# NoteGenerator.net
KiCad netlist of a schematic drawn in EAGLE
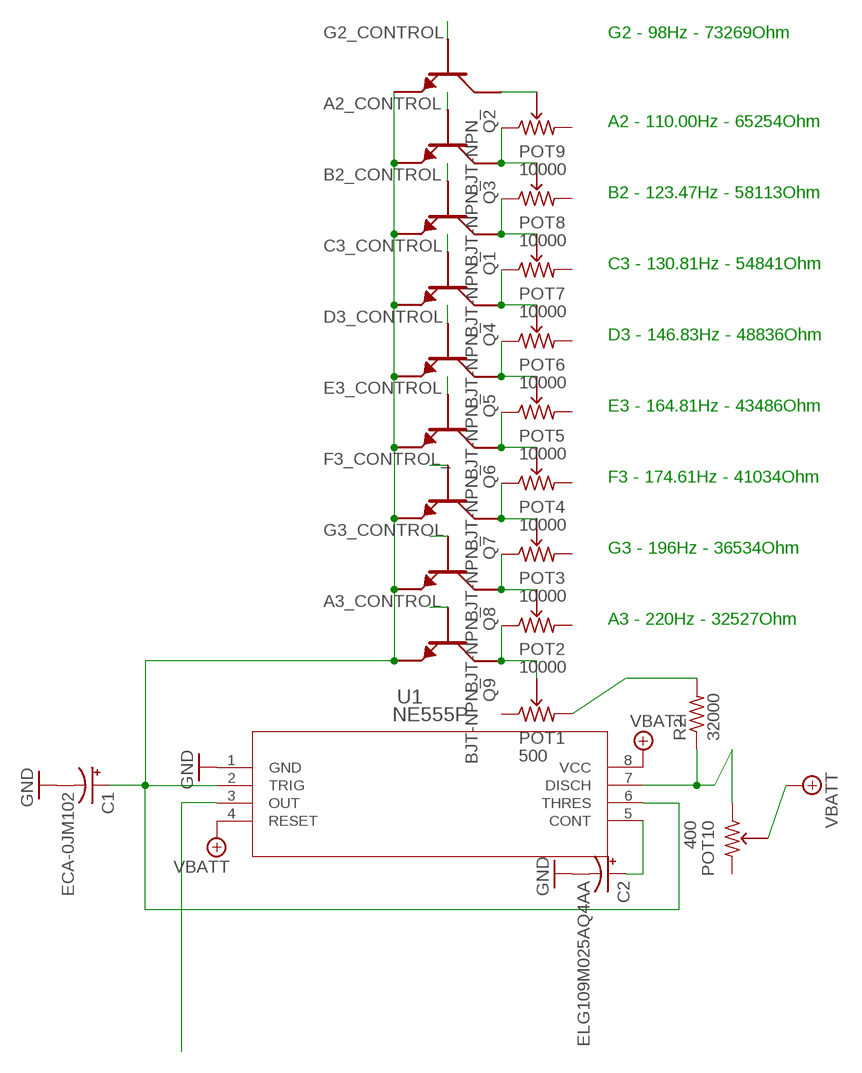
[diagram p0: schematic, sheet 1]

(export (version "E")
  (design (tool "Eeschema 10.0.6"))
  (components
    (comp (ref "C1")
      (value "ECA-0JM102")
      (footprint "eagle-import:PCAP_8X112")
      (fields (field (name "MANUFACTURER_PART_NUMBER") "ECA0JM102"))
      (libsource (lib "eagle-import") (part "ECA-0JM102"))
    )
    (comp (ref "C2")
      (value "ELG109M025AQ4AA")
      (footprint "eagle-import:PCAP_8X112")
      (fields (field (name "MANUFACTURER_PART_NUMBER") "ECA0JM102"))
      (libsource (lib "eagle-import") (part "ELG109M025AQ4AA"))
    )
    (comp (ref "POT1")
      (value "500")
      (footprint "eagle-import:PVG3G")
      (fields (field (name "POWER") "0.25W") (field (name "TOLERANCE") "±20%"))
      (libsource (lib "eagle-import") (part "PVG3"))
    )
    (comp (ref "POT2")
      (value "10000")
      (footprint "eagle-import:PVG3G")
      (fields (field (name "POWER") "0.25W") (field (name "TOLERANCE") "±20%"))
      (libsource (lib "eagle-import") (part "PVG3"))
    )
    (comp (ref "POT3")
      (value "10000")
      (footprint "eagle-import:PVG3G")
      (fields (field (name "POWER") "0.25W") (field (name "TOLERANCE") "±20%"))
      (libsource (lib "eagle-import") (part "PVG3"))
    )
    (comp (ref "POT4")
      (value "10000")
      (footprint "eagle-import:PVG3G")
      (fields (field (name "POWER") "0.25W") (field (name "TOLERANCE") "±20%"))
      (libsource (lib "eagle-import") (part "PVG3"))
    )
    (comp (ref "POT5")
      (value "10000")
      (footprint "eagle-import:PVG3G")
      (fields (field (name "POWER") "0.25W") (field (name "TOLERANCE") "±20%"))
      (libsource (lib "eagle-import") (part "PVG3"))
    )
    (comp (ref "POT6")
      (value "10000")
      (footprint "eagle-import:PVG3G")
      (fields (field (name "POWER") "0.25W") (field (name "TOLERANCE") "±20%"))
      (libsource (lib "eagle-import") (part "PVG3"))
    )
    (comp (ref "POT7")
      (value "10000")
      (footprint "eagle-import:PVG3G")
      (fields (field (name "POWER") "0.25W") (field (name "TOLERANCE") "±20%"))
      (libsource (lib "eagle-import") (part "PVG3"))
    )
    (comp (ref "POT8")
      (value "10000")
      (footprint "eagle-import:PVG3G")
      (fields (field (name "POWER") "0.25W") (field (name "TOLERANCE") "±20%"))
      (libsource (lib "eagle-import") (part "PVG3"))
    )
    (comp (ref "POT9")
      (value "10000")
      (footprint "eagle-import:PVG3G")
      (fields (field (name "POWER") "0.25W") (field (name "TOLERANCE") "±20%"))
      (libsource (lib "eagle-import") (part "PVG3"))
    )
    (comp (ref "POT10")
      (value "400")
      (footprint "eagle-import:PVG3G")
      (fields (field (name "POWER") "0.25W") (field (name "TOLERANCE") "±20%"))
      (libsource (lib "eagle-import") (part "PVG3"))
    )
    (comp (ref "Q1")
      (value "BJT-NPN_")
      (footprint "eagle-import:SOT-23-3")
      (libsource (lib "eagle-import") (part "BJT-NPN_"))
    )
    (comp (ref "Q2")
      (value "BJT-NPN_")
      (footprint "eagle-import:SOT-23-3")
      (libsource (lib "eagle-import") (part "BJT-NPN_"))
    )
    (comp (ref "Q3")
      (value "BJT-NPN_")
      (footprint "eagle-import:SOT-23-3")
      (libsource (lib "eagle-import") (part "BJT-NPN_"))
    )
    (comp (ref "Q4")
      (value "BJT-NPN_")
      (footprint "eagle-import:SOT-23-3")
      (libsource (lib "eagle-import") (part "BJT-NPN_"))
    )
    (comp (ref "Q5")
      (value "BJT-NPN_")
      (footprint "eagle-import:SOT-23-3")
      (libsource (lib "eagle-import") (part "BJT-NPN_"))
    )
    (comp (ref "Q6")
      (value "BJT-NPN_")
      (footprint "eagle-import:SOT-23-3")
      (libsource (lib "eagle-import") (part "BJT-NPN_"))
    )
    (comp (ref "Q7")
      (value "BJT-NPN_")
      (footprint "eagle-import:SOT-23-3")
      (libsource (lib "eagle-import") (part "BJT-NPN_"))
    )
    (comp (ref "Q8")
      (value "BJT-NPN_")
      (footprint "eagle-import:SOT-23-3")
      (libsource (lib "eagle-import") (part "BJT-NPN_"))
    )
    (comp (ref "Q9")
      (value "BJT-NPN_")
      (footprint "eagle-import:SOT-23-3")
      (libsource (lib "eagle-import") (part "BJT-NPN_"))
    )
    (comp (ref "R2")
      (value "32000")
      (footprint "eagle-import:RC0805N")
      (libsource (lib "eagle-import") (part "ERJ-L06KF50MV"))
    )
    (comp (ref "U1")
      (value "NE555P")
      (footprint "eagle-import:P8")
      (fields (field (name "GENERIC_PART_NUMBER") "NE555") (field (name "MANUFACTURER") "Texas Instruments"))
      (libsource (lib "eagle-import") (part "NE555P"))
    )
  )
  (nets
    (net (code "1") (name "/A2_CONTROL") (class "Default")
      (node (ref "Q3") (pin "1") (pinfunction "B_1") (pintype "bidirectional"))
    )
    (net (code "2") (name "/A3_CONTROL") (class "Default")
      (node (ref "Q9") (pin "1") (pinfunction "B_1") (pintype "bidirectional"))
    )
    (net (code "3") (name "/B2_CONTROL") (class "Default")
      (node (ref "Q1") (pin "1") (pinfunction "B_1") (pintype "bidirectional"))
    )
    (net (code "4") (name "/C3_CONTROL") (class "Default")
      (node (ref "Q4") (pin "1") (pinfunction "B_1") (pintype "bidirectional"))
    )
    (net (code "5") (name "/D3_CONTROL") (class "Default")
      (node (ref "Q5") (pin "1") (pinfunction "B_1") (pintype "bidirectional"))
    )
    (net (code "6") (name "/E3_CONTROL") (class "Default")
      (node (ref "Q6") (pin "1") (pinfunction "B_1") (pintype "bidirectional"))
    )
    (net (code "7") (name "/F3_CONTROL_") (class "Default")
      (node (ref "Q7") (pin "1") (pinfunction "B_1") (pintype "bidirectional"))
    )
    (net (code "8") (name "/G2_CONTROL") (class "Default")
      (node (ref "Q2") (pin "1") (pinfunction "B_1") (pintype "bidirectional"))
    )
    (net (code "9") (name "/G3_CONTROL") (class "Default")
      (node (ref "Q8") (pin "1") (pinfunction "B_1") (pintype "bidirectional"))
    )
    (net (code "10") (name "GND") (class "Default")
      (node (ref "C1") (pin "2") (pinfunction "-_2") (pintype "passive"))
      (node (ref "C2") (pin "2") (pinfunction "-_2") (pintype "passive"))
      (node (ref "U1") (pin "1") (pinfunction "GND_1") (pintype "power_in"))
    )
    (net (code "11") (name "Net-(C1-+)") (class "Default")
      (node (ref "C1") (pin "1") (pinfunction "+_1") (pintype "passive"))
      (node (ref "Q1") (pin "2") (pinfunction "E_2") (pintype "bidirectional"))
      (node (ref "Q2") (pin "2") (pinfunction "E_2") (pintype "bidirectional"))
      (node (ref "Q3") (pin "2") (pinfunction "E_2") (pintype "bidirectional"))
      (node (ref "Q4") (pin "2") (pinfunction "E_2") (pintype "bidirectional"))
      (node (ref "Q5") (pin "2") (pinfunction "E_2") (pintype "bidirectional"))
      (node (ref "Q6") (pin "2") (pinfunction "E_2") (pintype "bidirectional"))
      (node (ref "Q7") (pin "2") (pinfunction "E_2") (pintype "bidirectional"))
      (node (ref "Q8") (pin "2") (pinfunction "E_2") (pintype "bidirectional"))
      (node (ref "Q9") (pin "2") (pinfunction "E_2") (pintype "bidirectional"))
      (node (ref "U1") (pin "2") (pinfunction "TRIG_2") (pintype "input"))
      (node (ref "U1") (pin "6") (pinfunction "THRES_6") (pintype "input"))
    )
    (net (code "12") (name "Net-(C2-+)") (class "Default")
      (node (ref "C2") (pin "1") (pinfunction "+_1") (pintype "passive"))
      (node (ref "U1") (pin "5") (pinfunction "CONT_5") (pintype "passive"))
    )
    (net (code "13") (name "Net-(POT1-PIN2)") (class "Default")
      (node (ref "POT1") (pin "2") (pinfunction "PIN2_2") (pintype "passive"))
      (node (ref "POT2") (pin "1") (pinfunction "PIN1_1") (pintype "passive"))
      (node (ref "Q9") (pin "3") (pinfunction "C_3") (pintype "bidirectional"))
    )
    (net (code "14") (name "Net-(POT1-PIN3)") (class "Default")
      (node (ref "POT1") (pin "3") (pinfunction "PIN3_3") (pintype "passive"))
      (node (ref "R2") (pin "2") (pinfunction "PIN2_2") (pintype "passive"))
    )
    (net (code "15") (name "Net-(POT2-PIN2)") (class "Default")
      (node (ref "POT2") (pin "2") (pinfunction "PIN2_2") (pintype "passive"))
      (node (ref "POT3") (pin "1") (pinfunction "PIN1_1") (pintype "passive"))
      (node (ref "Q8") (pin "3") (pinfunction "C_3") (pintype "bidirectional"))
    )
    (net (code "16") (name "Net-(POT3-PIN2)") (class "Default")
      (node (ref "POT3") (pin "2") (pinfunction "PIN2_2") (pintype "passive"))
      (node (ref "POT4") (pin "1") (pinfunction "PIN1_1") (pintype "passive"))
      (node (ref "Q7") (pin "3") (pinfunction "C_3") (pintype "bidirectional"))
    )
    (net (code "17") (name "Net-(POT4-PIN2)") (class "Default")
      (node (ref "POT4") (pin "2") (pinfunction "PIN2_2") (pintype "passive"))
      (node (ref "POT5") (pin "1") (pinfunction "PIN1_1") (pintype "passive"))
      (node (ref "Q6") (pin "3") (pinfunction "C_3") (pintype "bidirectional"))
    )
    (net (code "18") (name "Net-(POT5-PIN2)") (class "Default")
      (node (ref "POT5") (pin "2") (pinfunction "PIN2_2") (pintype "passive"))
      (node (ref "POT6") (pin "1") (pinfunction "PIN1_1") (pintype "passive"))
      (node (ref "Q5") (pin "3") (pinfunction "C_3") (pintype "bidirectional"))
    )
    (net (code "19") (name "Net-(POT6-PIN2)") (class "Default")
      (node (ref "POT6") (pin "2") (pinfunction "PIN2_2") (pintype "passive"))
      (node (ref "POT7") (pin "1") (pinfunction "PIN1_1") (pintype "passive"))
      (node (ref "Q4") (pin "3") (pinfunction "C_3") (pintype "bidirectional"))
    )
    (net (code "20") (name "Net-(POT7-PIN2)") (class "Default")
      (node (ref "POT7") (pin "2") (pinfunction "PIN2_2") (pintype "passive"))
      (node (ref "POT8") (pin "1") (pinfunction "PIN1_1") (pintype "passive"))
      (node (ref "Q1") (pin "3") (pinfunction "C_3") (pintype "bidirectional"))
    )
    (net (code "21") (name "Net-(POT8-PIN2)") (class "Default")
      (node (ref "POT8") (pin "2") (pinfunction "PIN2_2") (pintype "passive"))
      (node (ref "POT9") (pin "1") (pinfunction "PIN1_1") (pintype "passive"))
      (node (ref "Q3") (pin "3") (pinfunction "C_3") (pintype "bidirectional"))
    )
    (net (code "22") (name "Net-(POT9-PIN2)") (class "Default")
      (node (ref "POT9") (pin "2") (pinfunction "PIN2_2") (pintype "passive"))
      (node (ref "Q2") (pin "3") (pinfunction "C_3") (pintype "bidirectional"))
    )
    (net (code "23") (name "Net-(POT10-PIN1)") (class "Default")
      (node (ref "POT10") (pin "1") (pinfunction "PIN1_1") (pintype "passive"))
      (node (ref "R2") (pin "1") (pinfunction "PIN1_1") (pintype "passive"))
      (node (ref "U1") (pin "7") (pinfunction "DISCH_7") (pintype "passive"))
    )
    (net (code "24") (name "VBATT") (class "Default")
      (node (ref "POT10") (pin "2") (pinfunction "PIN2_2") (pintype "passive"))
      (node (ref "U1") (pin "4") (pinfunction "RESET_4") (pintype "input"))
      (node (ref "U1") (pin "8") (pinfunction "VCC_8") (pintype "power_in"))
    )
    (net (code "25") (name "unconnected-(POT1-PIN1-Pad1)") (class "Default")
      (node (ref "POT1") (pin "1") (pinfunction "PIN1_1") (pintype "passive"))
    )
    (net (code "26") (name "unconnected-(POT2-PIN3-Pad3)") (class "Default")
      (node (ref "POT2") (pin "3") (pinfunction "PIN3_3") (pintype "passive"))
    )
    (net (code "27") (name "unconnected-(POT3-PIN3-Pad3)") (class "Default")
      (node (ref "POT3") (pin "3") (pinfunction "PIN3_3") (pintype "passive"))
    )
    (net (code "28") (name "unconnected-(POT4-PIN3-Pad3)") (class "Default")
      (node (ref "POT4") (pin "3") (pinfunction "PIN3_3") (pintype "passive"))
    )
    (net (code "29") (name "unconnected-(POT5-PIN3-Pad3)") (class "Default")
      (node (ref "POT5") (pin "3") (pinfunction "PIN3_3") (pintype "passive"))
    )
    (net (code "30") (name "unconnected-(POT6-PIN3-Pad3)") (class "Default")
      (node (ref "POT6") (pin "3") (pinfunction "PIN3_3") (pintype "passive"))
    )
    (net (code "31") (name "unconnected-(POT7-PIN3-Pad3)") (class "Default")
      (node (ref "POT7") (pin "3") (pinfunction "PIN3_3") (pintype "passive"))
    )
    (net (code "32") (name "unconnected-(POT8-PIN3-Pad3)") (class "Default")
      (node (ref "POT8") (pin "3") (pinfunction "PIN3_3") (pintype "passive"))
    )
    (net (code "33") (name "unconnected-(POT9-PIN3-Pad3)") (class "Default")
      (node (ref "POT9") (pin "3") (pinfunction "PIN3_3") (pintype "passive"))
    )
    (net (code "34") (name "unconnected-(POT10-PIN3-Pad3)") (class "Default")
      (node (ref "POT10") (pin "3") (pinfunction "PIN3_3") (pintype "passive"))
    )
    (net (code "35") (name "unconnected-(U1-OUT-Pad3)") (class "Default")
      (node (ref "U1") (pin "3") (pinfunction "OUT_3") (pintype "output"))
    )
  )
)
